# IMU_ISM330ISN.net
KiCad netlist of a schematic drawn in Altium Designer
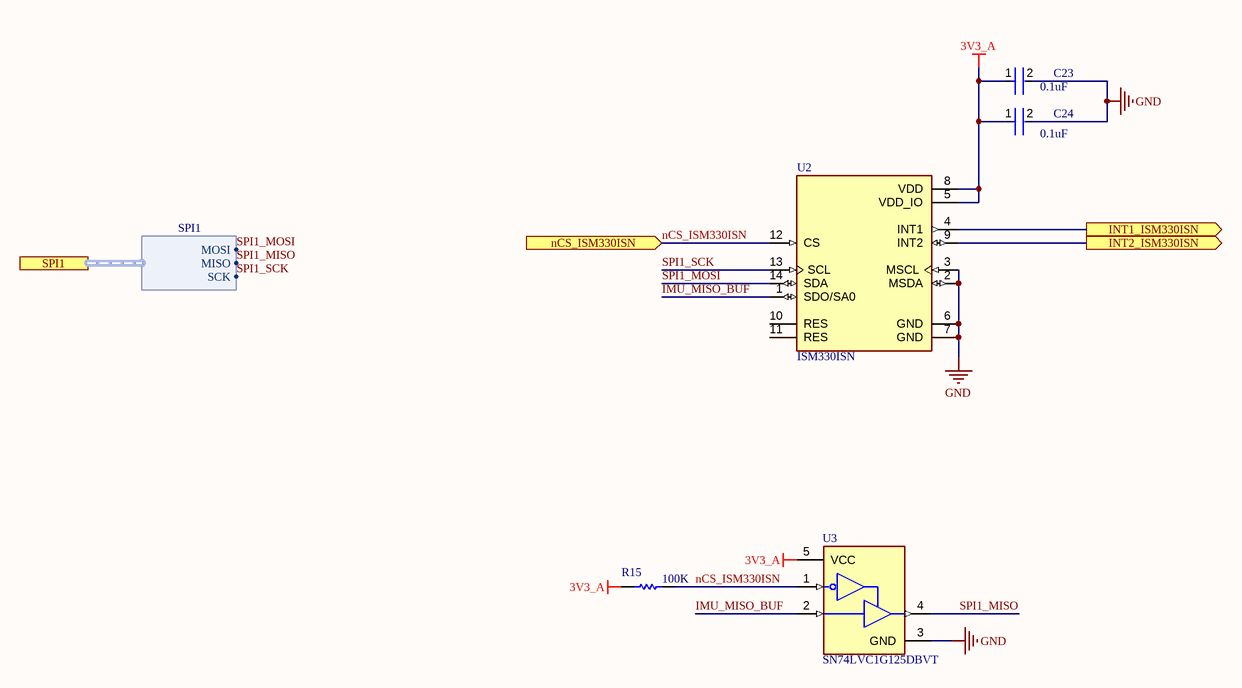
[diagram p0: IMU_ISM330ISN.SchDoc]

(export (version "E")
  (design (tool "Eeschema 10.0.6"))
  (components
    (comp (ref "C23")
      (value "0.1uF")
      (footprint "FP-C0603C-CF-MFG")
      (description "CAP CER 0.1UF 50V X7R 0603")
      (fields (field (name "TOLERANCE") "0.1") (field (name "MANUFACTURER") "KEMET"))
      (libsource (lib "Altium Content Vault") (part "b4654b650e69147ec39a6b967a45e02"))
    )
    (comp (ref "C24")
      (value "0.1uF")
      (footprint "FP-C0603C-CF-MFG")
      (description "CAP CER 0.1UF 50V X7R 0603")
      (fields (field (name "TOLERANCE") "0.1") (field (name "MANUFACTURER") "KEMET"))
      (libsource (lib "Altium Content Vault") (part "b4654b650e69147ec39a6b967a45e02"))
    )
    (comp (ref "R15")
      (value "100K")
      (footprint "RESC1608X55X30ML20T10")
      (fields (field (name "PART NUMBER") "RK73B1JTTD104J") (field (name "MANUFACTURER") "KOA Speer"))
      (libsource (lib "Altium Content Vault") (part "RES"))
    )
    (comp (ref "U2")
      (value "ISM330ISN")
      (footprint "XDCR_ISM330ISNTR")
      (description "Accelerometer, Gyroscope, Temperature, 6 Axis Sensor I2C, SPI Output")
      (fields (field (name "MF") "STMicroelectronics") (field (name "MP") "ISM330ISNTR"))
      (libsource (lib "Hitesh Bhoyar") (part "ISM330ISNTR"))
    )
    (comp (ref "U3")
      (value "SN74LVC1G125DBVT")
      (footprint "FP-DBV0005A-MFG")
      (description "IC BUF NON-INVERT 5.5V SOT23-5")
      (fields
        (field (name "OCTOPART") "https://octopart.com/sn74lvc1g125dbvt-texas+instruments-1006799")
        (field (name "MANUFACTURER") "Texas Instruments")
      )
      (libsource (lib "Altium Content Vault") (part "58769f6d8490b1ac5b52b989db43374"))
    )
  )
  (nets
    (net (code "2") (name "/IMU_MISO_BUF") (class "Default")
      (node (ref "U2") (pin "1") (pinfunction "SDO/SA0_1") (pintype "bidirectional"))
      (node (ref "U3") (pin "2") (pinfunction "A_2") (pintype "input"))
    )
    (net (code "3") (name "/INT1_ISM330ISN") (class "Default")
      (node (ref "U2") (pin "4") (pinfunction "INT1_4") (pintype "output"))
    )
    (net (code "4") (name "/INT2_ISM330ISN") (class "Default")
      (node (ref "U2") (pin "9") (pinfunction "INT2_9") (pintype "bidirectional"))
    )
    (net (code "5") (name "/SPI1_MISO") (class "Default")
      (node (ref "U3") (pin "4") (pinfunction "Y_4") (pintype "output"))
    )
    (net (code "6") (name "/SPI1_MOSI") (class "Default")
      (node (ref "U2") (pin "14") (pinfunction "SDA_14") (pintype "bidirectional"))
    )
    (net (code "7") (name "/SPI1_SCK") (class "Default")
      (node (ref "U2") (pin "13") (pinfunction "SCL_13") (pintype "input"))
    )
    (net (code "8") (name "/nCS_ISM330ISN") (class "Default")
      (node (ref "R15") (pin "1") (pinfunction "1_1") (pintype "passive"))
      (node (ref "U2") (pin "12") (pinfunction "CS_12") (pintype "input"))
      (node (ref "U3") (pin "1") (pinfunction "~{OE}_1") (pintype "input"))
    )
    (net (code "10") (name "3V3_A") (class "Default")
      (node (ref "C23") (pin "1") (pinfunction "1_1") (pintype "passive"))
      (node (ref "C24") (pin "1") (pinfunction "1_1") (pintype "passive"))
      (node (ref "R15") (pin "2") (pinfunction "2_2") (pintype "passive"))
      (node (ref "U2") (pin "5") (pinfunction "VDD_IO_5") (pintype "power_in"))
      (node (ref "U2") (pin "8") (pinfunction "VDD_8") (pintype "power_in"))
      (node (ref "U3") (pin "5") (pinfunction "VCC_5") (pintype "power_in"))
    )
    (net (code "11") (name "GND") (class "Default")
      (node (ref "C23") (pin "2") (pinfunction "2_2") (pintype "passive"))
      (node (ref "C24") (pin "2") (pinfunction "2_2") (pintype "passive"))
      (node (ref "U2") (pin "2") (pinfunction "MSDA_2") (pintype "bidirectional"))
      (node (ref "U2") (pin "3") (pinfunction "MSCL_3") (pintype "input"))
      (node (ref "U2") (pin "6") (pinfunction "GND_6") (pintype "power_in"))
      (node (ref "U2") (pin "7") (pinfunction "GND_7") (pintype "power_in"))
      (node (ref "U3") (pin "3") (pinfunction "GND_3") (pintype "power_in"))
    )
    (net (code "12") (name "unconnected-(U2-RES-Pad10)") (class "Default")
      (node (ref "U2") (pin "10") (pinfunction "RES_10") (pintype "passive"))
    )
    (net (code "13") (name "unconnected-(U2-RES-Pad11)") (class "Default")
      (node (ref "U2") (pin "11") (pinfunction "RES_11") (pintype "passive"))
    )
  )
)
